# motor.net
KiCad netlist of a schematic drawn in EAGLE
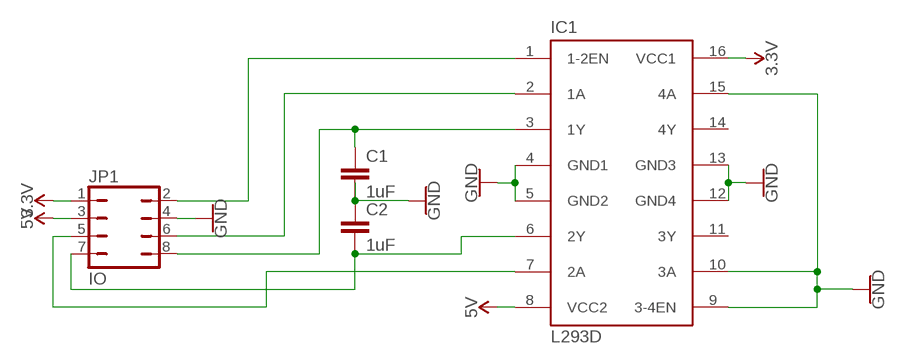
[diagram p0: schematic, sheet 1]

(export (version "E")
  (design (tool "Eeschema 10.0.6"))
  (components
    (comp (ref "C1")
      (value "1uF")
      (footprint "eagle-import:CAP-PTH-SMALL-KIT")
      (libsource (lib "eagle-import") (part "0.1UF-KIT-EZ-50V-20%"))
    )
    (comp (ref "C2")
      (value "1uF")
      (footprint "eagle-import:CAP-PTH-SMALL-KIT")
      (libsource (lib "eagle-import") (part "0.1UF-KIT-EZ-50V-20%"))
    )
    (comp (ref "IC1")
      (value "L293D")
      (footprint "eagle-import:DIL16")
      (libsource (lib "eagle-import") (part "L293D"))
    )
    (comp (ref "JP1")
      (value "IO")
      (footprint "eagle-import:JP4Q")
      (libsource (lib "eagle-import") (part "JP4Q"))
    )
  )
  (nets
    (net (code "1") (name "3.3V") (class "Default")
      (node (ref "IC1") (pin "16") (pinfunction "VCC1_16") (pintype "power_in"))
      (node (ref "JP1") (pin "1") (pinfunction "1_1") (pintype "passive"))
    )
    (net (code "2") (name "5V") (class "Default")
      (node (ref "IC1") (pin "8") (pinfunction "VCC2_8") (pintype "power_in"))
      (node (ref "JP1") (pin "3") (pinfunction "3_3") (pintype "passive"))
    )
    (net (code "3") (name "GND") (class "Default")
      (node (ref "C1") (pin "2") (pinfunction "2_2") (pintype "passive"))
      (node (ref "C2") (pin "1") (pinfunction "1_1") (pintype "passive"))
      (node (ref "IC1") (pin "10") (pinfunction "3A_10") (pintype "input"))
      (node (ref "IC1") (pin "12") (pinfunction "GND4_12") (pintype "power_in"))
      (node (ref "IC1") (pin "13") (pinfunction "GND3_13") (pintype "power_in"))
      (node (ref "IC1") (pin "15") (pinfunction "4A_15") (pintype "input"))
      (node (ref "IC1") (pin "4") (pinfunction "GND1_4") (pintype "power_in"))
      (node (ref "IC1") (pin "5") (pinfunction "GND2_5") (pintype "power_in"))
      (node (ref "IC1") (pin "9") (pinfunction "3-4EN_9") (pintype "input"))
      (node (ref "JP1") (pin "4") (pinfunction "4_4") (pintype "passive"))
    )
    (net (code "4") (name "Net-(IC1-1-2EN)") (class "Default")
      (node (ref "IC1") (pin "1") (pinfunction "1-2EN_1") (pintype "input"))
      (node (ref "JP1") (pin "2") (pinfunction "2_2") (pintype "passive"))
    )
    (net (code "5") (name "Net-(IC1-1A)") (class "Default")
      (node (ref "IC1") (pin "2") (pinfunction "1A_2") (pintype "input"))
      (node (ref "JP1") (pin "6") (pinfunction "6_6") (pintype "passive"))
    )
    (net (code "6") (name "Net-(IC1-1Y)") (class "Default")
      (node (ref "C1") (pin "1") (pinfunction "1_1") (pintype "passive"))
      (node (ref "IC1") (pin "3") (pinfunction "1Y_3") (pintype "output"))
      (node (ref "JP1") (pin "8") (pinfunction "8_8") (pintype "passive"))
    )
    (net (code "7") (name "Net-(IC1-2A)") (class "Default")
      (node (ref "IC1") (pin "7") (pinfunction "2A_7") (pintype "input"))
      (node (ref "JP1") (pin "5") (pinfunction "5_5") (pintype "passive"))
    )
    (net (code "8") (name "Net-(IC1-2Y)") (class "Default")
      (node (ref "C2") (pin "2") (pinfunction "2_2") (pintype "passive"))
      (node (ref "IC1") (pin "6") (pinfunction "2Y_6") (pintype "output"))
      (node (ref "JP1") (pin "7") (pinfunction "7_7") (pintype "passive"))
    )
    (net (code "9") (name "unconnected-(IC1-3Y-Pad11)") (class "Default")
      (node (ref "IC1") (pin "11") (pinfunction "3Y_11") (pintype "output"))
    )
    (net (code "10") (name "unconnected-(IC1-4Y-Pad14)") (class "Default")
      (node (ref "IC1") (pin "14") (pinfunction "4Y_14") (pintype "output"))
    )
  )
)
